# Gate_Drive.net
KiCad netlist of a schematic drawn in Altium Designer
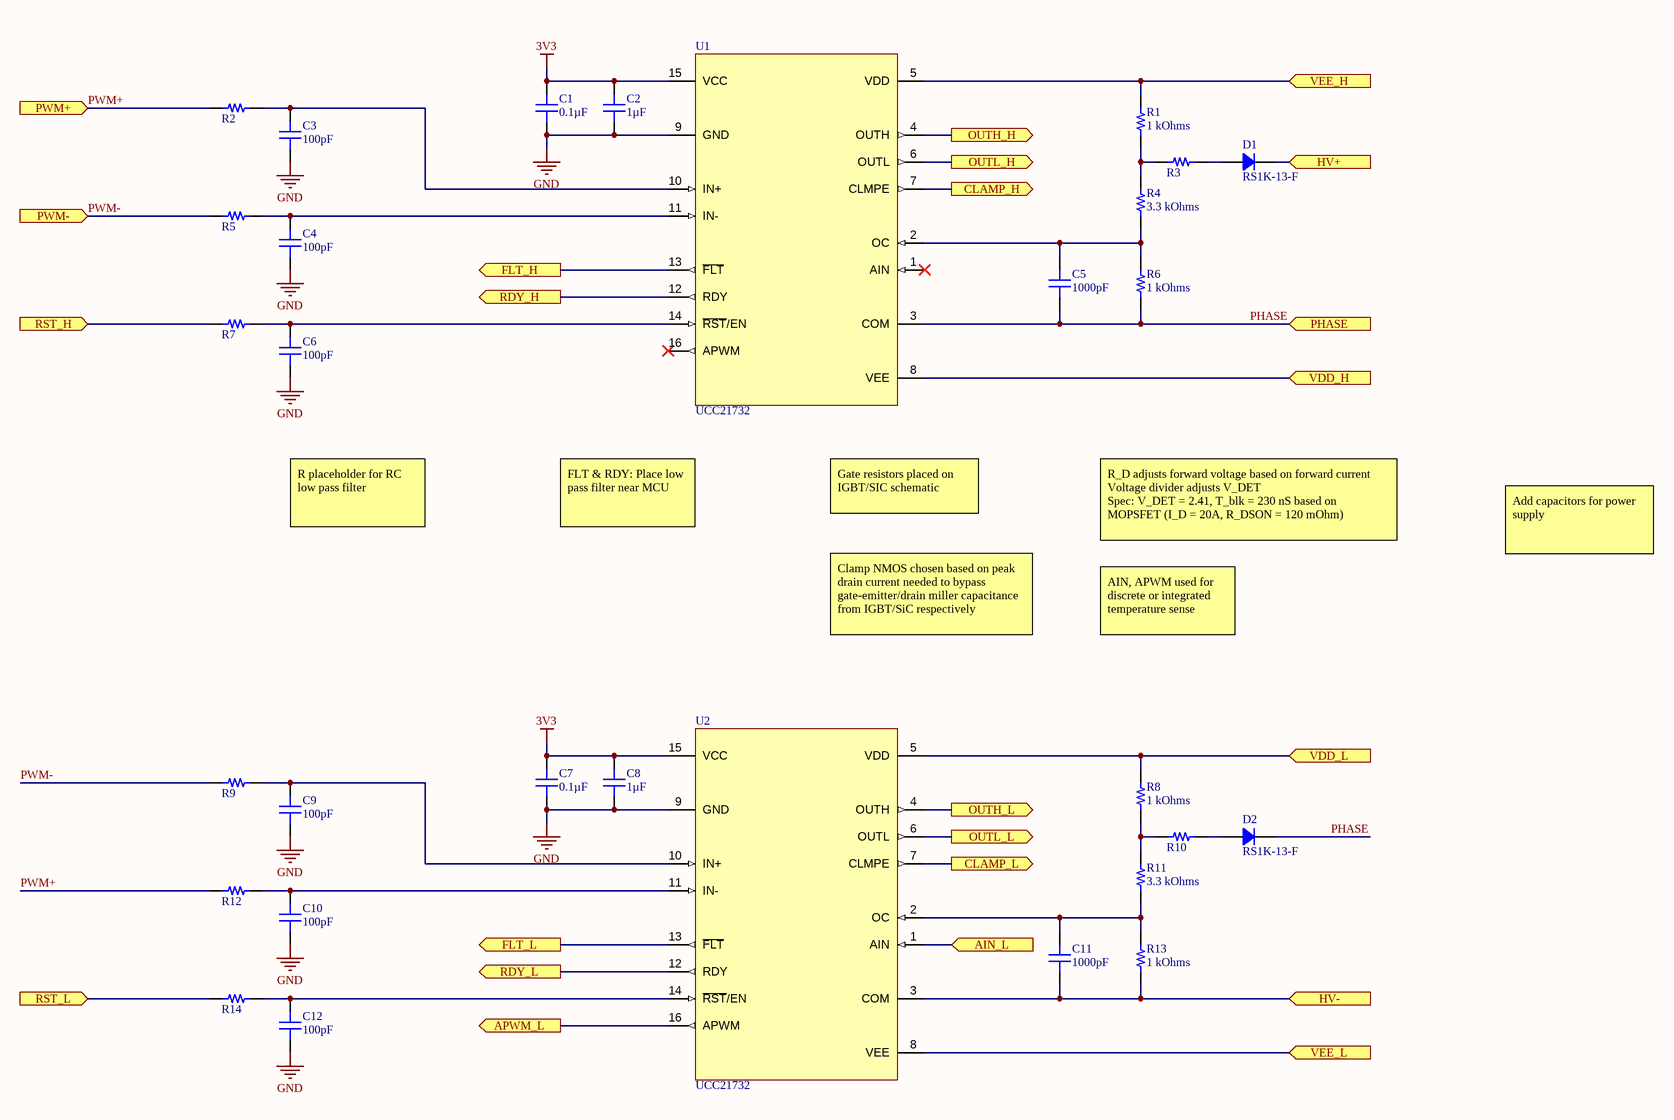
[diagram p0: Gate Drive.SchDoc]

(export (version "E")
  (design (tool "Eeschema 10.0.6"))
  (components
    (comp (ref "C1")
      (value "0.1µF")
      (footprint "CAP 0805_2012")
      (description "CAP CER 0.1UF 100V X7R 0805")
      (fields
        (field (name "PART NUMBER") "CGA4J2X7R2A104K125AE")
        (field (name "MANUFACTURER") "TDK Corporation")
      )
      (libsource (lib "Celestial Altium Library - altium_library") (part "Capacitor"))
    )
    (comp (ref "C2")
      (value "1µF")
      (footprint "CAP 0805_2012")
      (description "CAP CER 1UF 25V X7R 0805 EPOXY")
      (fields
        (field (name "PART NUMBER") "CGA4J3X7R1E105K125AD")
        (field (name "MANUFACTURER") "TDK Corporation")
      )
      (libsource (lib "Celestial Altium Library - altium_library") (part "Capacitor"))
    )
    (comp (ref "C3")
      (value "100pF")
      (footprint "CAP 0805_2012")
      (description "CAP CER 100PF 25V X7R 0805")
      (fields (field (name "PART NUMBER") "C0805C101K3RAC7800") (field (name "MANUFACTURER") "KEMET"))
      (libsource (lib "Celestial Altium Library - altium_library") (part "Capacitor"))
    )
    (comp (ref "C4")
      (value "100pF")
      (footprint "CAP 0805_2012")
      (description "CAP CER 100PF 25V X7R 0805")
      (fields (field (name "PART NUMBER") "C0805C101K3RAC7800") (field (name "MANUFACTURER") "KEMET"))
      (libsource (lib "Celestial Altium Library - altium_library") (part "Capacitor"))
    )
    (comp (ref "C5")
      (value "1000pF")
      (footprint "CAP 0805_2012")
      (description "CAP CER 1000PF 50V X7R 0805")
      (fields (field (name "PART NUMBER") "C0805C102J5RACTU") (field (name "MANUFACTURER") "KEMET"))
      (libsource (lib "Celestial Altium Library - altium_library") (part "Capacitor"))
    )
    (comp (ref "C6")
      (value "100pF")
      (footprint "CAP 0805_2012")
      (description "CAP CER 100PF 25V X7R 0805")
      (fields (field (name "PART NUMBER") "C0805C101K3RAC7800") (field (name "MANUFACTURER") "KEMET"))
      (libsource (lib "Celestial Altium Library - altium_library") (part "Capacitor"))
    )
    (comp (ref "C7")
      (value "0.1µF")
      (footprint "CAP 0805_2012")
      (description "CAP CER 0.1UF 100V X7R 0805")
      (fields
        (field (name "PART NUMBER") "CGA4J2X7R2A104K125AE")
        (field (name "MANUFACTURER") "TDK Corporation")
      )
      (libsource (lib "Celestial Altium Library - altium_library") (part "Capacitor"))
    )
    (comp (ref "C8")
      (value "1µF")
      (footprint "CAP 0805_2012")
      (description "CAP CER 1UF 25V X7R 0805 EPOXY")
      (fields
        (field (name "PART NUMBER") "CGA4J3X7R1E105K125AD")
        (field (name "MANUFACTURER") "TDK Corporation")
      )
      (libsource (lib "Celestial Altium Library - altium_library") (part "Capacitor"))
    )
    (comp (ref "C9")
      (value "100pF")
      (footprint "CAP 0805_2012")
      (description "CAP CER 100PF 25V X7R 0805")
      (fields (field (name "PART NUMBER") "C0805C101K3RAC7800") (field (name "MANUFACTURER") "KEMET"))
      (libsource (lib "Celestial Altium Library - altium_library") (part "Capacitor"))
    )
    (comp (ref "C10")
      (value "100pF")
      (footprint "CAP 0805_2012")
      (description "CAP CER 100PF 25V X7R 0805")
      (fields (field (name "PART NUMBER") "C0805C101K3RAC7800") (field (name "MANUFACTURER") "KEMET"))
      (libsource (lib "Celestial Altium Library - altium_library") (part "Capacitor"))
    )
    (comp (ref "C11")
      (value "1000pF")
      (footprint "CAP 0805_2012")
      (description "CAP CER 1000PF 50V X7R 0805")
      (fields (field (name "PART NUMBER") "C0805C102J5RACTU") (field (name "MANUFACTURER") "KEMET"))
      (libsource (lib "Celestial Altium Library - altium_library") (part "Capacitor"))
    )
    (comp (ref "C12")
      (value "100pF")
      (footprint "CAP 0805_2012")
      (description "CAP CER 100PF 25V X7R 0805")
      (fields (field (name "PART NUMBER") "C0805C101K3RAC7800") (field (name "MANUFACTURER") "KEMET"))
      (libsource (lib "Celestial Altium Library - altium_library") (part "Capacitor"))
    )
    (comp (ref "D1")
      (value "RS1K-13-F")
      (footprint "DO214AC SMA")
      (description "DIODE GEN PURP 800V 1A SMA")
      (fields (field (name "MANUFACTURER") "Diodes Incorporated"))
      (libsource (lib "Celestial Altium Library - altium_library") (part "Diode"))
    )
    (comp (ref "D2")
      (value "RS1K-13-F")
      (footprint "DO214AC SMA")
      (description "DIODE GEN PURP 800V 1A SMA")
      (fields (field (name "MANUFACTURER") "Diodes Incorporated"))
      (libsource (lib "Celestial Altium Library - altium_library") (part "Diode"))
    )
    (comp (ref "R1")
      (value "1 kOhms")
      (footprint "RES 0805_2012")
      (description "RES SMD 1K OHM 5% 1/2W 0805")
      (fields (field (name "PART NUMBER") "CRCW08051K00JNEAHP") (field (name "MANUFACTURER") "Vishay Dale"))
      (libsource (lib "Celestial Altium Library - altium_library") (part "Resistor"))
    )
    (comp (ref "R2")
      (value "~")
      (footprint "RES 0805_2012")
      (description "RES 0 OHM JUMPER 0805")
      (fields (field (name "PART NUMBER") "5107") (field (name "MANUFACTURER") "Keystone Electronics"))
      (libsource (lib "Celestial Altium Library - altium_library") (part "Resistor"))
    )
    (comp (ref "R3")
      (value "~")
      (footprint "RES 0805_2012")
      (description "RES 0 OHM JUMPER 0805")
      (fields (field (name "PART NUMBER") "5107") (field (name "MANUFACTURER") "Keystone Electronics"))
      (libsource (lib "Celestial Altium Library - altium_library") (part "Resistor"))
    )
    (comp (ref "R4")
      (value "3.3 kOhms")
      (footprint "RES 0805_2012")
      (description "RES SMD 3.3K OHM 5% 1/8W 0805")
      (fields (field (name "PART NUMBER") "CRCW08053K30JNEA") (field (name "MANUFACTURER") "Vishay Dale"))
      (libsource (lib "Celestial Altium Library - altium_library") (part "Resistor"))
    )
    (comp (ref "R5")
      (value "~")
      (footprint "RES 0805_2012")
      (description "RES 0 OHM JUMPER 0805")
      (fields (field (name "PART NUMBER") "5107") (field (name "MANUFACTURER") "Keystone Electronics"))
      (libsource (lib "Celestial Altium Library - altium_library") (part "Resistor"))
    )
    (comp (ref "R6")
      (value "1 kOhms")
      (footprint "RES 0805_2012")
      (description "RES SMD 1K OHM 5% 1/2W 0805")
      (fields (field (name "PART NUMBER") "CRCW08051K00JNEAHP") (field (name "MANUFACTURER") "Vishay Dale"))
      (libsource (lib "Celestial Altium Library - altium_library") (part "Resistor"))
    )
    (comp (ref "R7")
      (value "~")
      (footprint "RES 0805_2012")
      (description "RES 0 OHM JUMPER 0805")
      (fields (field (name "PART NUMBER") "5107") (field (name "MANUFACTURER") "Keystone Electronics"))
      (libsource (lib "Celestial Altium Library - altium_library") (part "Resistor"))
    )
    (comp (ref "R8")
      (value "1 kOhms")
      (footprint "RES 0805_2012")
      (description "RES SMD 1K OHM 5% 1/2W 0805")
      (fields (field (name "PART NUMBER") "CRCW08051K00JNEAHP") (field (name "MANUFACTURER") "Vishay Dale"))
      (libsource (lib "Celestial Altium Library - altium_library") (part "Resistor"))
    )
    (comp (ref "R9")
      (value "~")
      (footprint "RES 0805_2012")
      (description "RES 0 OHM JUMPER 0805")
      (fields (field (name "PART NUMBER") "5107") (field (name "MANUFACTURER") "Keystone Electronics"))
      (libsource (lib "Celestial Altium Library - altium_library") (part "Resistor"))
    )
    (comp (ref "R10")
      (value "~")
      (footprint "RES 0805_2012")
      (description "RES 0 OHM JUMPER 0805")
      (fields (field (name "PART NUMBER") "5107") (field (name "MANUFACTURER") "Keystone Electronics"))
      (libsource (lib "Celestial Altium Library - altium_library") (part "Resistor"))
    )
    (comp (ref "R11")
      (value "3.3 kOhms")
      (footprint "RES 0805_2012")
      (description "RES SMD 3.3K OHM 5% 1/8W 0805")
      (fields (field (name "PART NUMBER") "CRCW08053K30JNEA") (field (name "MANUFACTURER") "Vishay Dale"))
      (libsource (lib "Celestial Altium Library - altium_library") (part "Resistor"))
    )
    (comp (ref "R12")
      (value "~")
      (footprint "RES 0805_2012")
      (description "RES 0 OHM JUMPER 0805")
      (fields (field (name "PART NUMBER") "5107") (field (name "MANUFACTURER") "Keystone Electronics"))
      (libsource (lib "Celestial Altium Library - altium_library") (part "Resistor"))
    )
    (comp (ref "R13")
      (value "1 kOhms")
      (footprint "RES 0805_2012")
      (description "RES SMD 1K OHM 5% 1/2W 0805")
      (fields (field (name "PART NUMBER") "CRCW08051K00JNEAHP") (field (name "MANUFACTURER") "Vishay Dale"))
      (libsource (lib "Celestial Altium Library - altium_library") (part "Resistor"))
    )
    (comp (ref "R14")
      (value "~")
      (footprint "RES 0805_2012")
      (description "RES 0 OHM JUMPER 0805")
      (fields (field (name "PART NUMBER") "5107") (field (name "MANUFACTURER") "Keystone Electronics"))
      (libsource (lib "Celestial Altium Library - altium_library") (part "Resistor"))
    )
    (comp (ref "U1")
      (value "UCC21732")
      (description "10A Gate Driver Capacitive Coupling 5700Vrms 1 Channel 16-SOIC")
      (libsource (lib "3PO") (part "UCC21732"))
    )
    (comp (ref "U2")
      (value "UCC21732")
      (description "10A Gate Driver Capacitive Coupling 5700Vrms 1 Channel 16-SOIC")
      (libsource (lib "3PO") (part "UCC21732"))
    )
  )
  (nets
    (net (code "1") (name "/AIN_L") (class "Default")
      (node (ref "U2") (pin "1") (pinfunction "AIN_1") (pintype "input"))
    )
    (net (code "2") (name "/APWM_L") (class "Default")
      (node (ref "U2") (pin "16") (pinfunction "APWM_16") (pintype "output"))
    )
    (net (code "3") (name "/CLAMP_H") (class "Default")
      (node (ref "U1") (pin "7") (pinfunction "CLMPE_7") (pintype "output"))
    )
    (net (code "4") (name "/CLAMP_L") (class "Default")
      (node (ref "U2") (pin "7") (pinfunction "CLMPE_7") (pintype "output"))
    )
    (net (code "5") (name "/FLT_H") (class "Default")
      (node (ref "U1") (pin "13") (pinfunction "~{FLT}_13") (pintype "output"))
    )
    (net (code "6") (name "/FLT_L") (class "Default")
      (node (ref "U2") (pin "13") (pinfunction "~{FLT}_13") (pintype "output"))
    )
    (net (code "7") (name "/HV+") (class "Default")
      (node (ref "D1") (pin "2") (pinfunction "2_2") (pintype "passive"))
    )
    (net (code "8") (name "/HV-") (class "Default")
      (node (ref "C11") (pin "1") (pinfunction "1_1") (pintype "passive"))
      (node (ref "R13") (pin "1") (pinfunction "1_1") (pintype "passive"))
      (node (ref "U2") (pin "3") (pinfunction "COM_3") (pintype "power_in"))
    )
    (net (code "9") (name "/OUTH_H") (class "Default")
      (node (ref "U1") (pin "4") (pinfunction "OUTH_4") (pintype "output"))
    )
    (net (code "10") (name "/OUTH_L") (class "Default")
      (node (ref "U2") (pin "4") (pinfunction "OUTH_4") (pintype "output"))
    )
    (net (code "11") (name "/OUTL_H") (class "Default")
      (node (ref "U1") (pin "6") (pinfunction "OUTL_6") (pintype "output"))
    )
    (net (code "12") (name "/OUTL_L") (class "Default")
      (node (ref "U2") (pin "6") (pinfunction "OUTL_6") (pintype "output"))
    )
    (net (code "13") (name "/PHASE") (class "Default")
      (node (ref "C5") (pin "1") (pinfunction "1_1") (pintype "passive"))
      (node (ref "D2") (pin "2") (pinfunction "2_2") (pintype "passive"))
      (node (ref "R6") (pin "1") (pinfunction "1_1") (pintype "passive"))
      (node (ref "U1") (pin "3") (pinfunction "COM_3") (pintype "power_in"))
    )
    (net (code "14") (name "/PWM+") (class "Default")
      (node (ref "R12") (pin "1") (pinfunction "1_1") (pintype "passive"))
      (node (ref "R2") (pin "1") (pinfunction "1_1") (pintype "passive"))
    )
    (net (code "15") (name "/PWM-") (class "Default")
      (node (ref "R5") (pin "1") (pinfunction "1_1") (pintype "passive"))
      (node (ref "R9") (pin "1") (pinfunction "1_1") (pintype "passive"))
    )
    (net (code "16") (name "/RDY_H") (class "Default")
      (node (ref "U1") (pin "12") (pinfunction "RDY_12") (pintype "output"))
    )
    (net (code "17") (name "/RDY_L") (class "Default")
      (node (ref "U2") (pin "12") (pinfunction "RDY_12") (pintype "output"))
    )
    (net (code "18") (name "/RST_H") (class "Default")
      (node (ref "R7") (pin "1") (pinfunction "1_1") (pintype "passive"))
    )
    (net (code "19") (name "/RST_L") (class "Default")
      (node (ref "R14") (pin "1") (pinfunction "1_1") (pintype "passive"))
    )
    (net (code "20") (name "/VDD_H") (class "Default")
      (node (ref "U1") (pin "8") (pinfunction "VEE_8") (pintype "power_in"))
    )
    (net (code "21") (name "/VDD_L") (class "Default")
      (node (ref "R8") (pin "2") (pinfunction "2_2") (pintype "passive"))
      (node (ref "U2") (pin "5") (pinfunction "VDD_5") (pintype "power_in"))
    )
    (net (code "22") (name "/VEE_H") (class "Default")
      (node (ref "R1") (pin "2") (pinfunction "2_2") (pintype "passive"))
      (node (ref "U1") (pin "5") (pinfunction "VDD_5") (pintype "power_in"))
    )
    (net (code "23") (name "/VEE_L") (class "Default")
      (node (ref "U2") (pin "8") (pinfunction "VEE_8") (pintype "power_in"))
    )
    (net (code "24") (name "3V3") (class "Default")
      (node (ref "C1") (pin "2") (pinfunction "2_2") (pintype "passive"))
      (node (ref "C2") (pin "2") (pinfunction "2_2") (pintype "passive"))
      (node (ref "C7") (pin "2") (pinfunction "2_2") (pintype "passive"))
      (node (ref "C8") (pin "2") (pinfunction "2_2") (pintype "passive"))
      (node (ref "U1") (pin "15") (pinfunction "VCC_15") (pintype "power_in"))
      (node (ref "U2") (pin "15") (pinfunction "VCC_15") (pintype "power_in"))
    )
    (net (code "25") (name "GND") (class "Default")
      (node (ref "C1") (pin "1") (pinfunction "1_1") (pintype "passive"))
      (node (ref "C10") (pin "1") (pinfunction "1_1") (pintype "passive"))
      (node (ref "C12") (pin "1") (pinfunction "1_1") (pintype "passive"))
      (node (ref "C2") (pin "1") (pinfunction "1_1") (pintype "passive"))
      (node (ref "C3") (pin "1") (pinfunction "1_1") (pintype "passive"))
      (node (ref "C4") (pin "1") (pinfunction "1_1") (pintype "passive"))
      (node (ref "C6") (pin "1") (pinfunction "1_1") (pintype "passive"))
      (node (ref "C7") (pin "1") (pinfunction "1_1") (pintype "passive"))
      (node (ref "C8") (pin "1") (pinfunction "1_1") (pintype "passive"))
      (node (ref "C9") (pin "1") (pinfunction "1_1") (pintype "passive"))
      (node (ref "U1") (pin "9") (pinfunction "GND_9") (pintype "power_in"))
      (node (ref "U2") (pin "9") (pinfunction "GND_9") (pintype "power_in"))
    )
    (net (code "26") (name "Net-(D1-Pad1)") (class "Default")
      (node (ref "D1") (pin "1") (pinfunction "1_1") (pintype "passive"))
      (node (ref "R3") (pin "2") (pinfunction "2_2") (pintype "passive"))
    )
    (net (code "27") (name "Net-(D2-Pad1)") (class "Default")
      (node (ref "D2") (pin "1") (pinfunction "1_1") (pintype "passive"))
      (node (ref "R10") (pin "2") (pinfunction "2_2") (pintype "passive"))
    )
    (net (code "28") (name "Net-(R1-Pad1)") (class "Default")
      (node (ref "R1") (pin "1") (pinfunction "1_1") (pintype "passive"))
      (node (ref "R3") (pin "1") (pinfunction "1_1") (pintype "passive"))
      (node (ref "R4") (pin "2") (pinfunction "2_2") (pintype "passive"))
    )
    (net (code "29") (name "Net-(R10-Pad1)") (class "Default")
      (node (ref "R10") (pin "1") (pinfunction "1_1") (pintype "passive"))
      (node (ref "R11") (pin "2") (pinfunction "2_2") (pintype "passive"))
      (node (ref "R8") (pin "1") (pinfunction "1_1") (pintype "passive"))
    )
    (net (code "30") (name "Net-(U1-IN+)") (class "Default")
      (node (ref "C3") (pin "2") (pinfunction "2_2") (pintype "passive"))
      (node (ref "R2") (pin "2") (pinfunction "2_2") (pintype "passive"))
      (node (ref "U1") (pin "10") (pinfunction "IN+_10") (pintype "input"))
    )
    (net (code "31") (name "Net-(U1-IN-)") (class "Default")
      (node (ref "C4") (pin "2") (pinfunction "2_2") (pintype "passive"))
      (node (ref "R5") (pin "2") (pinfunction "2_2") (pintype "passive"))
      (node (ref "U1") (pin "11") (pinfunction "IN-_11") (pintype "input"))
    )
    (net (code "32") (name "Net-(U1-OC)") (class "Default")
      (node (ref "C5") (pin "2") (pinfunction "2_2") (pintype "passive"))
      (node (ref "R4") (pin "1") (pinfunction "1_1") (pintype "passive"))
      (node (ref "R6") (pin "2") (pinfunction "2_2") (pintype "passive"))
      (node (ref "U1") (pin "2") (pinfunction "OC_2") (pintype "input"))
    )
    (net (code "33") (name "Net-(U1-~{RST}{slash}EN)") (class "Default")
      (node (ref "C6") (pin "2") (pinfunction "2_2") (pintype "passive"))
      (node (ref "R7") (pin "2") (pinfunction "2_2") (pintype "passive"))
      (node (ref "U1") (pin "14") (pinfunction "~{RST}/EN_14") (pintype "input"))
    )
    (net (code "34") (name "Net-(U2-IN+)") (class "Default")
      (node (ref "C9") (pin "2") (pinfunction "2_2") (pintype "passive"))
      (node (ref "R9") (pin "2") (pinfunction "2_2") (pintype "passive"))
      (node (ref "U2") (pin "10") (pinfunction "IN+_10") (pintype "input"))
    )
    (net (code "35") (name "Net-(U2-IN-)") (class "Default")
      (node (ref "C10") (pin "2") (pinfunction "2_2") (pintype "passive"))
      (node (ref "R12") (pin "2") (pinfunction "2_2") (pintype "passive"))
      (node (ref "U2") (pin "11") (pinfunction "IN-_11") (pintype "input"))
    )
    (net (code "36") (name "Net-(U2-OC)") (class "Default")
      (node (ref "C11") (pin "2") (pinfunction "2_2") (pintype "passive"))
      (node (ref "R11") (pin "1") (pinfunction "1_1") (pintype "passive"))
      (node (ref "R13") (pin "2") (pinfunction "2_2") (pintype "passive"))
      (node (ref "U2") (pin "2") (pinfunction "OC_2") (pintype "input"))
    )
    (net (code "37") (name "Net-(U2-~{RST}{slash}EN)") (class "Default")
      (node (ref "C12") (pin "2") (pinfunction "2_2") (pintype "passive"))
      (node (ref "R14") (pin "2") (pinfunction "2_2") (pintype "passive"))
      (node (ref "U2") (pin "14") (pinfunction "~{RST}/EN_14") (pintype "input"))
    )
    (net (code "38") (name "unconnected-(U1-AIN-Pad1)") (class "Default")
      (node (ref "U1") (pin "1") (pinfunction "AIN_1") (pintype "input+no_connect"))
    )
    (net (code "39") (name "unconnected-(U1-APWM-Pad16)") (class "Default")
      (node (ref "U1") (pin "16") (pinfunction "APWM_16") (pintype "output+no_connect"))
    )
  )
)
